# LSM6DS3_Breakout.net
KiCad netlist of a schematic drawn in EAGLE
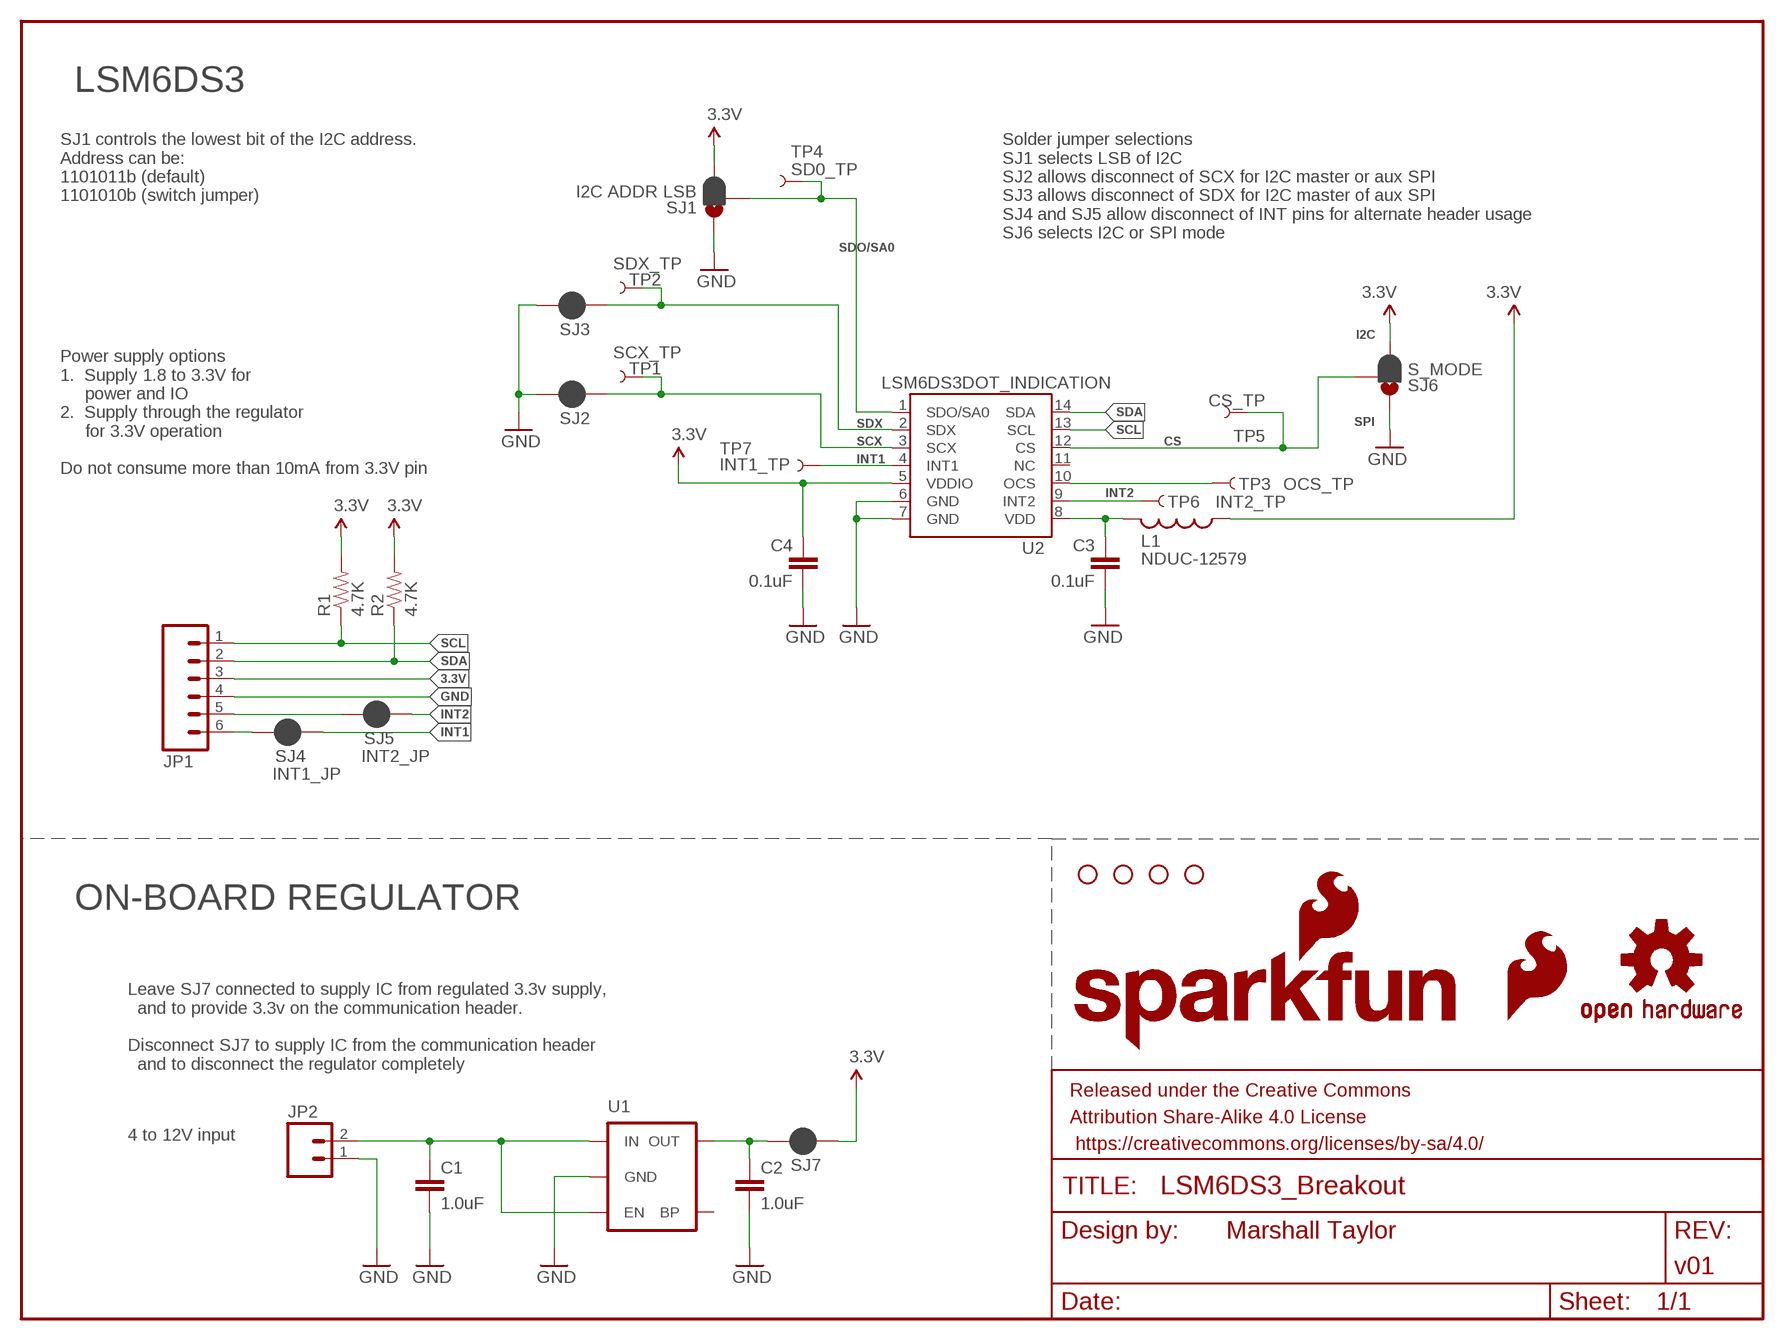
[diagram p0: schematic, sheet 1]

(export (version "E")
  (design (tool "Eeschema 10.0.6"))
  (components
    (comp (ref "C1")
      (value "1.0uF")
      (footprint "eagle-import:0603-CAP")
      (libsource (lib "eagle-import") (part "1.0UF-16V-10%(0603)"))
    )
    (comp (ref "C2")
      (value "1.0uF")
      (footprint "eagle-import:0603-CAP")
      (libsource (lib "eagle-import") (part "1.0UF-16V-10%(0603)"))
    )
    (comp (ref "C3")
      (value "0.1uF")
      (footprint "eagle-import:0603-CAP")
      (libsource (lib "eagle-import") (part "0.1UF-100V-10%(0603)"))
    )
    (comp (ref "C4")
      (value "0.1uF")
      (footprint "eagle-import:0603-CAP")
      (libsource (lib "eagle-import") (part "0.1UF-100V-10%(0603)"))
    )
    (comp (ref "FRAME1")
      (value "FRAME-LETTER")
      (footprint "eagle-import:CREATIVE_COMMONS")
      (fields
        (field (name "DESIGNER") "Marshall Taylor")
        (field (name "VERSION") "v01")
        (field (name "DESIGNER_1") "Marshall Taylor")
      )
      (libsource (lib "eagle-import") (part "FRAME-LETTER"))
    )
    (comp (ref "JP1")
      (value "M06SILK_FEMALE_PTH")
      (footprint "eagle-import:1X06")
      (libsource (lib "eagle-import") (part "M06SILK_FEMALE_PTH"))
    )
    (comp (ref "JP2")
      (value "M02PTH")
      (footprint "eagle-import:1X02")
      (libsource (lib "eagle-import") (part "M02PTH"))
    )
    (comp (ref "L1")
      (value "NDUC-12579")
      (footprint "eagle-import:0603")
      (libsource (lib "eagle-import") (part "INDUCTOR0603"))
    )
    (comp (ref "LOGO1")
      (value "SFE_LOGO_NAME_FLAME.1_INCH")
      (footprint "eagle-import:SFE_LOGO_NAME_FLAME_.1")
      (libsource (lib "eagle-import") (part "SFE_LOGO_NAME_FLAME.1_INCH"))
    )
    (comp (ref "LOGO2")
      (value "OSHW-LOGOS")
      (footprint "eagle-import:OSHW-LOGO-S")
      (libsource (lib "eagle-import") (part "OSHW-LOGOS"))
    )
    (comp (ref "LOGO3")
      (value "SFE_LOGO_FLAME.4_INCH")
      (footprint "eagle-import:SFE_LOGO_FLAME_.4")
      (libsource (lib "eagle-import") (part "SFE_LOGO_FLAME.4_INCH"))
    )
    (comp (ref "R1")
      (value "4.7K")
      (footprint "eagle-import:0603-RES")
      (libsource (lib "eagle-import") (part "4.7KOHM-1/10W-1%(0603)"))
    )
    (comp (ref "R2")
      (value "4.7K")
      (footprint "eagle-import:0603-RES")
      (libsource (lib "eagle-import") (part "4.7KOHM-1/10W-1%(0603)"))
    )
    (comp (ref "SJ1")
      (value "I2C ADDR LSB")
      (footprint "eagle-import:PAD-JUMPER-3-2OF3_NC_BY_PASTE_YES_SILK_FULL_BOX")
      (libsource (lib "eagle-import") (part "JUMPER-PAD-3-2OF3_NC_BY_PASTE"))
    )
    (comp (ref "SJ2")
      (value "JUMPER-PAD-2-NC_BY_PASTE")
      (footprint "eagle-import:PAD-JUMPER-2-NC_BY_PASTE_YES_SILK")
      (libsource (lib "eagle-import") (part "JUMPER-PAD-2-NC_BY_PASTE"))
    )
    (comp (ref "SJ3")
      (value "JUMPER-PAD-2-NC_BY_PASTE")
      (footprint "eagle-import:PAD-JUMPER-2-NC_BY_PASTE_YES_SILK")
      (libsource (lib "eagle-import") (part "JUMPER-PAD-2-NC_BY_PASTE"))
    )
    (comp (ref "SJ4")
      (value "INT1_JP")
      (footprint "eagle-import:PAD-JUMPER-2-NC_BY_PASTE_YES_SILK")
      (libsource (lib "eagle-import") (part "JUMPER-PAD-2-NC_BY_PASTE"))
    )
    (comp (ref "SJ5")
      (value "INT2_JP")
      (footprint "eagle-import:PAD-JUMPER-2-NC_BY_PASTE_YES_SILK")
      (libsource (lib "eagle-import") (part "JUMPER-PAD-2-NC_BY_PASTE"))
    )
    (comp (ref "SJ6")
      (value "S_MODE")
      (footprint "eagle-import:PAD-JUMPER-3-2OF3_NC_BY_PASTE_YES_SILK_FULL_BOX")
      (libsource (lib "eagle-import") (part "JUMPER-PAD-3-2OF3_NC_BY_PASTE"))
    )
    (comp (ref "SJ7")
      (value "JUMPER-PAD-2-NC_BY_PASTE")
      (footprint "eagle-import:PAD-JUMPER-2-NC_BY_PASTE_YES_SILK")
      (libsource (lib "eagle-import") (part "JUMPER-PAD-2-NC_BY_PASTE"))
    )
    (comp (ref "STANDOFF1")
      (value "STAND-OFF")
      (footprint "eagle-import:STAND-OFF")
      (libsource (lib "eagle-import") (part "STAND-OFF"))
    )
    (comp (ref "STANDOFF2")
      (value "STAND-OFF")
      (footprint "eagle-import:STAND-OFF")
      (libsource (lib "eagle-import") (part "STAND-OFF"))
    )
    (comp (ref "STANDOFF3")
      (value "STAND-OFF")
      (footprint "eagle-import:STAND-OFF")
      (libsource (lib "eagle-import") (part "STAND-OFF"))
    )
    (comp (ref "STANDOFF4")
      (value "STAND-OFF")
      (footprint "eagle-import:STAND-OFF")
      (libsource (lib "eagle-import") (part "STAND-OFF"))
    )
    (comp (ref "TP1")
      (value "SCX_TP")
      (footprint "eagle-import:TP_15TH")
      (libsource (lib "eagle-import") (part "TEST-POINTTP_15TH_THRU"))
    )
    (comp (ref "TP2")
      (value "SDX_TP")
      (footprint "eagle-import:TP_15TH")
      (libsource (lib "eagle-import") (part "TEST-POINTTP_15TH_THRU"))
    )
    (comp (ref "TP3")
      (value "OCS_TP")
      (footprint "eagle-import:TP_15TH")
      (libsource (lib "eagle-import") (part "TEST-POINTTP_15TH_THRU"))
    )
    (comp (ref "TP4")
      (value "SD0_TP")
      (footprint "eagle-import:TP_15TH")
      (libsource (lib "eagle-import") (part "TEST-POINTTP_15TH_THRU"))
    )
    (comp (ref "TP5")
      (value "CS_TP")
      (footprint "eagle-import:TP_15TH")
      (libsource (lib "eagle-import") (part "TEST-POINTTP_15TH_THRU"))
    )
    (comp (ref "TP6")
      (value "INT2_TP")
      (footprint "eagle-import:TP_15TH")
      (libsource (lib "eagle-import") (part "TEST-POINTTP_15TH_THRU"))
    )
    (comp (ref "TP7")
      (value "INT1_TP")
      (footprint "eagle-import:TP_15TH")
      (libsource (lib "eagle-import") (part "TEST-POINTTP_15TH_THRU"))
    )
    (comp (ref "U1")
      (value "MIC52053.3V")
      (footprint "eagle-import:SOT23-5")
      (libsource (lib "eagle-import") (part "MIC52053.3V"))
    )
    (comp (ref "U2")
      (value "LSM6DS3DOT_INDICATION")
      (footprint "eagle-import:LGA14L_DOT_INDICATOR")
      (libsource (lib "eagle-import") (part "LSM6DS3DOT_INDICATION"))
    )
  )
  (nets
    (net (code "1") (name "/CS") (class "Default")
      (node (ref "SJ6") (pin "2") (pinfunction "2_2") (pintype "passive"))
      (node (ref "TP5") (pin "P$1") (pinfunction "1_P$1") (pintype "bidirectional"))
      (node (ref "U2") (pin "12") (pinfunction "CS_12") (pintype "bidirectional"))
    )
    (net (code "2") (name "/SCX") (class "Default")
      (node (ref "SJ2") (pin "1") (pinfunction "1_1") (pintype "passive"))
      (node (ref "TP1") (pin "P$1") (pinfunction "1_P$1") (pintype "bidirectional"))
      (node (ref "U2") (pin "3") (pinfunction "SCX_3") (pintype "bidirectional"))
    )
    (net (code "3") (name "/SDO{slash}SA0") (class "Default")
      (node (ref "SJ1") (pin "2") (pinfunction "2_2") (pintype "passive"))
      (node (ref "TP4") (pin "P$1") (pinfunction "1_P$1") (pintype "bidirectional"))
      (node (ref "U2") (pin "1") (pinfunction "SDO/SA0_1") (pintype "bidirectional"))
    )
    (net (code "4") (name "/SDX") (class "Default")
      (node (ref "SJ3") (pin "1") (pinfunction "1_1") (pintype "passive"))
      (node (ref "TP2") (pin "P$1") (pinfunction "1_P$1") (pintype "bidirectional"))
      (node (ref "U2") (pin "2") (pinfunction "SDX_2") (pintype "bidirectional"))
    )
    (net (code "5") (name "3.3V") (class "Default")
      (node (ref "C4") (pin "1") (pinfunction "1_1") (pintype "passive"))
      (node (ref "JP1") (pin "3") (pinfunction "3_3") (pintype "passive"))
      (node (ref "L1") (pin "1") (pinfunction "1_1") (pintype "passive"))
      (node (ref "R1") (pin "2") (pinfunction "2_2") (pintype "passive"))
      (node (ref "R2") (pin "2") (pinfunction "2_2") (pintype "passive"))
      (node (ref "SJ1") (pin "3") (pinfunction "3_3") (pintype "passive"))
      (node (ref "SJ6") (pin "3") (pinfunction "3_3") (pintype "passive"))
      (node (ref "SJ7") (pin "1") (pinfunction "1_1") (pintype "passive"))
      (node (ref "U2") (pin "5") (pinfunction "VDDIO_5") (pintype "bidirectional"))
    )
    (net (code "6") (name "GND") (class "Default")
      (node (ref "C1") (pin "2") (pinfunction "2_2") (pintype "passive"))
      (node (ref "C2") (pin "2") (pinfunction "2_2") (pintype "passive"))
      (node (ref "C3") (pin "2") (pinfunction "2_2") (pintype "passive"))
      (node (ref "C4") (pin "2") (pinfunction "2_2") (pintype "passive"))
      (node (ref "JP1") (pin "4") (pinfunction "4_4") (pintype "passive"))
      (node (ref "JP2") (pin "1") (pinfunction "1_1") (pintype "passive"))
      (node (ref "SJ1") (pin "1") (pinfunction "1_1") (pintype "passive"))
      (node (ref "SJ2") (pin "2") (pinfunction "2_2") (pintype "passive"))
      (node (ref "SJ3") (pin "2") (pinfunction "2_2") (pintype "passive"))
      (node (ref "SJ6") (pin "1") (pinfunction "1_1") (pintype "passive"))
      (node (ref "U1") (pin "2") (pinfunction "GND_2") (pintype "input"))
      (node (ref "U2") (pin "6") (pinfunction "GND_6") (pintype "bidirectional"))
      (node (ref "U2") (pin "7") (pinfunction "GND_7") (pintype "bidirectional"))
    )
    (net (code "7") (name "INT1") (class "Default")
      (node (ref "SJ4") (pin "1") (pinfunction "1_1") (pintype "passive"))
      (node (ref "TP7") (pin "P$1") (pinfunction "1_P$1") (pintype "bidirectional"))
      (node (ref "U2") (pin "4") (pinfunction "INT1_4") (pintype "bidirectional"))
    )
    (net (code "8") (name "INT2") (class "Default")
      (node (ref "SJ5") (pin "1") (pinfunction "1_1") (pintype "passive"))
      (node (ref "TP6") (pin "P$1") (pinfunction "1_P$1") (pintype "bidirectional"))
      (node (ref "U2") (pin "9") (pinfunction "INT2_9") (pintype "bidirectional"))
    )
    (net (code "9") (name "Net-(JP1-Pad5)") (class "Default")
      (node (ref "JP1") (pin "5") (pinfunction "5_5") (pintype "passive"))
      (node (ref "SJ5") (pin "2") (pinfunction "2_2") (pintype "passive"))
    )
    (net (code "10") (name "Net-(JP1-Pad6)") (class "Default")
      (node (ref "JP1") (pin "6") (pinfunction "6_6") (pintype "passive"))
      (node (ref "SJ4") (pin "2") (pinfunction "2_2") (pintype "passive"))
    )
    (net (code "11") (name "Net-(TP3-1)") (class "Default")
      (node (ref "TP3") (pin "P$1") (pinfunction "1_P$1") (pintype "bidirectional"))
      (node (ref "U2") (pin "10") (pinfunction "OCS_10") (pintype "bidirectional"))
    )
    (net (code "12") (name "Net-(U1-EN)") (class "Default")
      (node (ref "C1") (pin "1") (pinfunction "1_1") (pintype "passive"))
      (node (ref "JP2") (pin "2") (pinfunction "2_2") (pintype "passive"))
      (node (ref "U1") (pin "1") (pinfunction "IN_1") (pintype "input"))
      (node (ref "U1") (pin "3") (pinfunction "EN_3") (pintype "input"))
    )
    (net (code "13") (name "Net-(U1-OUT)") (class "Default")
      (node (ref "C2") (pin "1") (pinfunction "1_1") (pintype "passive"))
      (node (ref "SJ7") (pin "2") (pinfunction "2_2") (pintype "passive"))
      (node (ref "U1") (pin "5") (pinfunction "OUT_5") (pintype "passive"))
    )
    (net (code "14") (name "Net-(U2-VDD)") (class "Default")
      (node (ref "C3") (pin "1") (pinfunction "1_1") (pintype "passive"))
      (node (ref "L1") (pin "2") (pinfunction "2_2") (pintype "passive"))
      (node (ref "U2") (pin "8") (pinfunction "VDD_8") (pintype "bidirectional"))
    )
    (net (code "15") (name "SCL") (class "Default")
      (node (ref "JP1") (pin "1") (pinfunction "1_1") (pintype "passive"))
      (node (ref "R1") (pin "1") (pinfunction "1_1") (pintype "passive"))
      (node (ref "U2") (pin "13") (pinfunction "SCL_13") (pintype "bidirectional"))
    )
    (net (code "16") (name "SDA") (class "Default")
      (node (ref "JP1") (pin "2") (pinfunction "2_2") (pintype "passive"))
      (node (ref "R2") (pin "1") (pinfunction "1_1") (pintype "passive"))
      (node (ref "U2") (pin "14") (pinfunction "SDA_14") (pintype "bidirectional"))
    )
    (net (code "17") (name "unconnected-(U1-BP-Pad4)") (class "Default")
      (node (ref "U1") (pin "4") (pinfunction "BP_4") (pintype "input"))
    )
    (net (code "18") (name "unconnected-(U2-NC-Pad11)") (class "Default")
      (node (ref "U2") (pin "11") (pinfunction "NC_11") (pintype "bidirectional"))
    )
  )
)
